# Power_Modem_Breakout.net
KiCad netlist of a schematic drawn in EAGLE
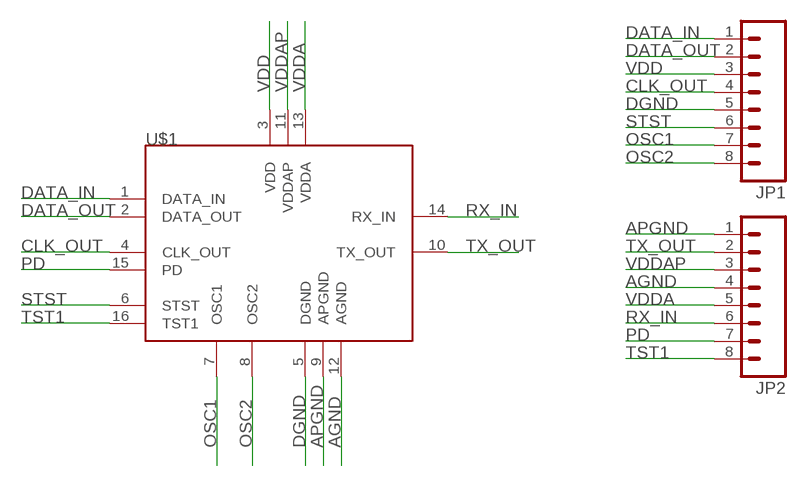
[diagram p0: schematic, sheet 1]

(export (version "E")
  (design (tool "Eeschema 10.0.6"))
  (components
    (comp (ref "JP1")
      (value "M08LONGPADS")
      (footprint "eagle-import:1X08_LONGPADS")
      (libsource (lib "eagle-import") (part "M08LONGPADS"))
    )
    (comp (ref "JP2")
      (value "M08LONGPADS")
      (footprint "eagle-import:1X08_LONGPADS")
      (libsource (lib "eagle-import") (part "M08LONGPADS"))
    )
    (comp (ref "U$1")
      (value "TDA5052AT")
      (footprint "eagle-import:SO16L")
      (libsource (lib "eagle-import") (part "TDA5052AT"))
    )
  )
  (nets
    (net (code "1") (name "/AGND") (class "Default")
      (node (ref "JP2") (pin "4") (pinfunction "4_4") (pintype "passive"))
      (node (ref "U$1") (pin "12") (pinfunction "AGND_12") (pintype "bidirectional"))
    )
    (net (code "2") (name "/APGND") (class "Default")
      (node (ref "JP2") (pin "1") (pinfunction "1_1") (pintype "passive"))
      (node (ref "U$1") (pin "9") (pinfunction "APGND_9") (pintype "bidirectional"))
    )
    (net (code "3") (name "/CLK_OUT") (class "Default")
      (node (ref "JP1") (pin "4") (pinfunction "4_4") (pintype "passive"))
      (node (ref "U$1") (pin "4") (pinfunction "CLK_OUT_4") (pintype "bidirectional"))
    )
    (net (code "4") (name "/DATA_IN") (class "Default")
      (node (ref "JP1") (pin "1") (pinfunction "1_1") (pintype "passive"))
      (node (ref "U$1") (pin "1") (pinfunction "DATA_IN_1") (pintype "bidirectional"))
    )
    (net (code "5") (name "/DATA_OUT") (class "Default")
      (node (ref "JP1") (pin "2") (pinfunction "2_2") (pintype "passive"))
      (node (ref "U$1") (pin "2") (pinfunction "DATA_OUT_2") (pintype "bidirectional"))
    )
    (net (code "6") (name "/DGND") (class "Default")
      (node (ref "JP1") (pin "5") (pinfunction "5_5") (pintype "passive"))
      (node (ref "U$1") (pin "5") (pinfunction "DGND_5") (pintype "bidirectional"))
    )
    (net (code "7") (name "/OSC1") (class "Default")
      (node (ref "JP1") (pin "7") (pinfunction "7_7") (pintype "passive"))
      (node (ref "U$1") (pin "7") (pinfunction "OSC1_7") (pintype "bidirectional"))
    )
    (net (code "8") (name "/OSC2") (class "Default")
      (node (ref "JP1") (pin "8") (pinfunction "8_8") (pintype "passive"))
      (node (ref "U$1") (pin "8") (pinfunction "OSC2_8") (pintype "bidirectional"))
    )
    (net (code "9") (name "/PD") (class "Default")
      (node (ref "JP2") (pin "7") (pinfunction "7_7") (pintype "passive"))
      (node (ref "U$1") (pin "15") (pinfunction "PD_15") (pintype "bidirectional"))
    )
    (net (code "10") (name "/RX_IN") (class "Default")
      (node (ref "JP2") (pin "6") (pinfunction "6_6") (pintype "passive"))
      (node (ref "U$1") (pin "14") (pinfunction "RX_IN_14") (pintype "bidirectional"))
    )
    (net (code "11") (name "/STST") (class "Default")
      (node (ref "JP1") (pin "6") (pinfunction "6_6") (pintype "passive"))
      (node (ref "U$1") (pin "6") (pinfunction "STST_6") (pintype "bidirectional"))
    )
    (net (code "12") (name "/TST1") (class "Default")
      (node (ref "JP2") (pin "8") (pinfunction "8_8") (pintype "passive"))
      (node (ref "U$1") (pin "16") (pinfunction "TST1_16") (pintype "bidirectional"))
    )
    (net (code "13") (name "/TX_OUT") (class "Default")
      (node (ref "JP2") (pin "2") (pinfunction "2_2") (pintype "passive"))
      (node (ref "U$1") (pin "10") (pinfunction "TX_OUT_10") (pintype "bidirectional"))
    )
    (net (code "14") (name "/VDD") (class "Default")
      (node (ref "JP1") (pin "3") (pinfunction "3_3") (pintype "passive"))
      (node (ref "U$1") (pin "3") (pinfunction "VDD_3") (pintype "bidirectional"))
    )
    (net (code "15") (name "/VDDA") (class "Default")
      (node (ref "JP2") (pin "5") (pinfunction "5_5") (pintype "passive"))
      (node (ref "U$1") (pin "13") (pinfunction "VDDA_13") (pintype "bidirectional"))
    )
    (net (code "16") (name "/VDDAP") (class "Default")
      (node (ref "JP2") (pin "3") (pinfunction "3_3") (pintype "passive"))
      (node (ref "U$1") (pin "11") (pinfunction "VDDAP_11") (pintype "bidirectional"))
    )
  )
)
